# TOP_LEVEL.net
KiCad netlist of a schematic drawn in Altium Designer
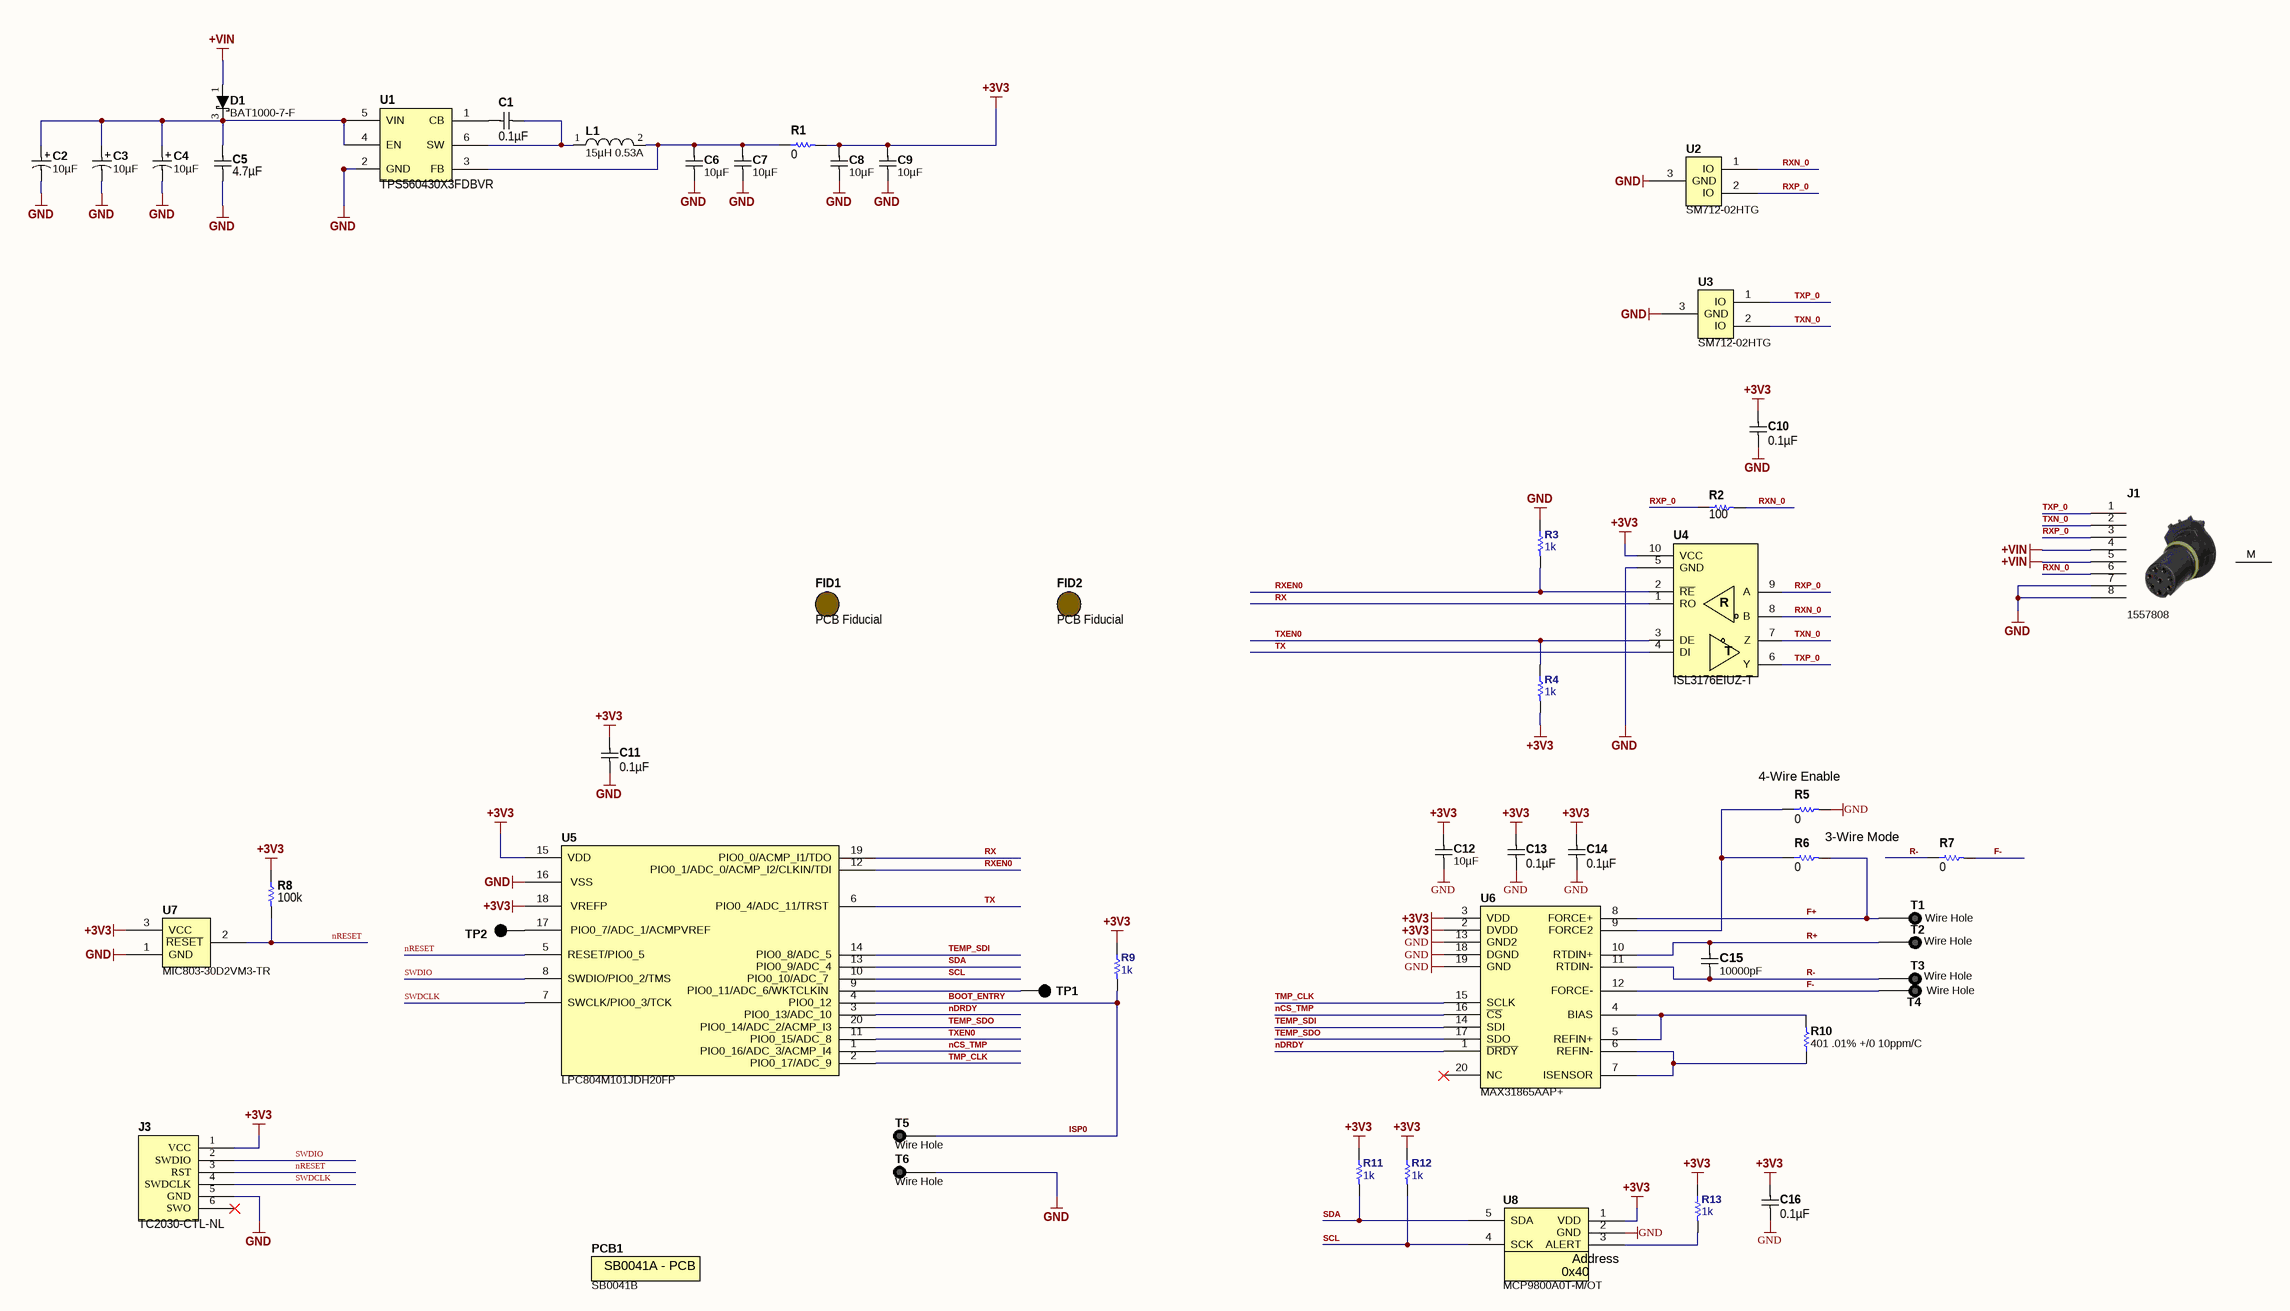
[diagram p0: TOP_LEVEL.SCHDOC]

(export (version "E")
  (design (tool "Eeschema 10.0.6"))
  (components
    (comp (ref "C1")
      (value "0.1µF")
      (footprint "C0603_0.90MM_MD")
      (description "CAP CER 0.1UF 50V X7R 0603")
      (fields
        (field (name "MANUFACTURER PART NUMBER") "CGA3E2X7R1H104K080AE")
        (field (name "MANUFACTURER") "TDK Corporation")
      )
      (libsource (lib "Capacitors - TDK- AEC-Q200") (part "C_2P_NP"))
    )
    (comp (ref "C2")
      (value "10µF")
      (footprint "C_ALU_B")
      (description "CAP ALUM 10UF 35V 20% SMD")
      (fields
        (field (name "MANUFACTURER PART NUMBER") "EEE-FK1V100UR")
        (field (name "MANUFACTURER") "Panasonic Electronic Components")
      )
      (libsource (lib "Capacitors - Panasonic - AluminumElectrolytic - AEC-Q200") (part "C_2P_P"))
    )
    (comp (ref "C3")
      (value "10µF")
      (footprint "C_ALU_B")
      (description "CAP ALUM 10UF 35V 20% SMD")
      (fields
        (field (name "MANUFACTURER PART NUMBER") "EEE-FK1V100UR")
        (field (name "MANUFACTURER") "Panasonic Electronic Components")
      )
      (libsource (lib "Capacitors - Panasonic - AluminumElectrolytic - AEC-Q200") (part "C_2P_P"))
    )
    (comp (ref "C4")
      (value "10µF")
      (footprint "C_ALU_B")
      (description "CAP ALUM 10UF 35V 20% SMD")
      (fields
        (field (name "MANUFACTURER PART NUMBER") "EEE-FK1V100UR")
        (field (name "MANUFACTURER") "Panasonic Electronic Components")
      )
      (libsource (lib "Capacitors - Panasonic - AluminumElectrolytic - AEC-Q200") (part "C_2P_P"))
    )
    (comp (ref "C5")
      (value "4.7µF")
      (footprint "C0805_1.50MM_MD")
      (description "CAP CER 4.7UF 35V X7R 0805")
      (fields
        (field (name "MANUFACTURER PART NUMBER") "CGA4J1X7R1V475K125AE")
        (field (name "MANUFACTURER") "TDK Corporation")
      )
      (libsource (lib "Capacitors - TDK- AEC-Q200") (part "C_2P_NP"))
    )
    (comp (ref "C6")
      (value "10µF")
      (footprint "C0805_1.25MM_MD")
      (description "CAP CER 10UF 6.3V X7R 0805")
      (fields
        (field (name "MANUFACTURER PART NUMBER") "CGA4J1X7R0J106K125AD")
        (field (name "MANUFACTURER") "TDK Corporation")
      )
      (libsource (lib "Capacitors - TDK- AEC-Q200") (part "C_2P_NP"))
    )
    (comp (ref "C7")
      (value "10µF")
      (footprint "C0805_1.25MM_MD")
      (description "CAP CER 10UF 6.3V X7R 0805")
      (fields
        (field (name "MANUFACTURER PART NUMBER") "CGA4J1X7R0J106K125AD")
        (field (name "MANUFACTURER") "TDK Corporation")
      )
      (libsource (lib "Capacitors - TDK- AEC-Q200") (part "C_2P_NP"))
    )
    (comp (ref "C8")
      (value "10µF")
      (footprint "C0805_1.25MM_MD")
      (description "CAP CER 10UF 6.3V X7R 0805")
      (fields
        (field (name "MANUFACTURER PART NUMBER") "CGA4J1X7R0J106K125AD")
        (field (name "MANUFACTURER") "TDK Corporation")
      )
      (libsource (lib "Capacitors - TDK- AEC-Q200") (part "C_2P_NP"))
    )
    (comp (ref "C9")
      (value "10µF")
      (footprint "C0805_1.25MM_MD")
      (description "CAP CER 10UF 6.3V X7R 0805")
      (fields
        (field (name "MANUFACTURER PART NUMBER") "CGA4J1X7R0J106K125AD")
        (field (name "MANUFACTURER") "TDK Corporation")
      )
      (libsource (lib "Capacitors - TDK- AEC-Q200") (part "C_2P_NP"))
    )
    (comp (ref "C10")
      (value "0.1µF")
      (footprint "C0603_0.90MM_MD")
      (description "CAP CER 0.1UF 50V X7R 0603")
      (fields
        (field (name "MANUFACTURER PART NUMBER") "CGA3E2X7R1H104K080AE")
        (field (name "MANUFACTURER") "TDK Corporation")
      )
      (libsource (lib "Capacitors - TDK- AEC-Q200") (part "C_2P_NP"))
    )
    (comp (ref "C11")
      (value "0.1µF")
      (footprint "C0603_0.90MM_MD")
      (description "CAP CER 0.1UF 50V X7R 0603")
      (fields
        (field (name "MANUFACTURER PART NUMBER") "CGA3E2X7R1H104K080AE")
        (field (name "MANUFACTURER") "TDK Corporation")
      )
      (libsource (lib "Capacitors - TDK- AEC-Q200") (part "C_2P_NP"))
    )
    (comp (ref "C12")
      (value "10µF")
      (footprint "C0805_1.25MM_MD")
      (description "CAP CER 10UF 6.3V X7R 0805")
      (fields
        (field (name "MANUFACTURER PART NUMBER") "CGA4J1X7R0J106K125AD")
        (field (name "MANUFACTURER") "TDK Corporation")
      )
      (libsource (lib "Capacitors - TDK- AEC-Q200") (part "C_2P_NP"))
    )
    (comp (ref "C13")
      (value "0.1µF")
      (footprint "C0603_0.90MM_MD")
      (description "CAP CER 0.1UF 50V X7R 0603")
      (fields
        (field (name "MANUFACTURER PART NUMBER") "CGA3E2X7R1H104K080AE")
        (field (name "MANUFACTURER") "TDK Corporation")
      )
      (libsource (lib "Capacitors - TDK- AEC-Q200") (part "C_2P_NP"))
    )
    (comp (ref "C14")
      (value "0.1µF")
      (footprint "C0603_0.90MM_MD")
      (description "CAP CER 0.1UF 50V X7R 0603")
      (fields
        (field (name "MANUFACTURER PART NUMBER") "CGA3E2X7R1H104K080AE")
        (field (name "MANUFACTURER") "TDK Corporation")
      )
      (libsource (lib "Capacitors - TDK- AEC-Q200") (part "C_2P_NP"))
    )
    (comp (ref "C15")
      (value "10000pF")
      (footprint "C0603_0.90MM_HD")
      (description "CAP CER 10000PF 50V X7R 0603")
      (fields
        (field (name "MANUFACTURER PART NUMBER") "AC0603KPX7R9BB103")
        (field (name "MANUFACTURER") "Yageo")
      )
      (libsource (lib "Capacitors - Yageo - AEC-Q200") (part "C_2P_NP"))
    )
    (comp (ref "C16")
      (value "0.1µF")
      (footprint "C0603_0.90MM_MD")
      (description "CAP CER 0.1UF 50V X7R 0603")
      (fields
        (field (name "MANUFACTURER PART NUMBER") "CGA3E2X7R1H104K080AE")
        (field (name "MANUFACTURER") "TDK Corporation")
      )
      (libsource (lib "Capacitors - TDK- AEC-Q200") (part "C_2P_NP"))
    )
    (comp (ref "D1")
      (value "BAT1000-7-F")
      (footprint "D_SOT-23-3_P")
      (description "DIODE SCHOTTKY 40V 1A SOT23")
      (fields (field (name "MANUFACTURER") "Diodes Inc"))
      (libsource (lib "Diodes") (part "DS_1A_3C"))
    )
    (comp (ref "FID1")
      (value "PCB Fiducial")
      (footprint "Fiducial 1mm - 2mm")
      (libsource (lib "eFiducial") (part "Fiducial"))
    )
    (comp (ref "FID2")
      (value "PCB Fiducial")
      (footprint "Fiducial 1mm - 2mm")
      (libsource (lib "eFiducial") (part "Fiducial"))
    )
    (comp (ref "J1")
      (value "1557808")
      (footprint "1557808")
      (description "Circular Metric Connectors SACC-CI-M12FS -8CON-L180-THR")
      (fields (field (name "MANUFACTURER") "Phoenix Contact"))
      (libsource (lib "eConnector_Phoenix_M12") (part "1557808"))
    )
    (comp (ref "J3")
      (value "TC2030‐CTL‐NL")
      (footprint "TC2030")
      (description "Tag Connect Pads - No latching Clips - ARM")
      (libsource (lib "eConnector") (part "TC2030‐CTL‐NL"))
    )
    (comp (ref "L1")
      (value "15µH 0.53A")
      (footprint "L_NRH3012")
      (description "Inductor 15µH 0.53A")
      (fields
        (field (name "MANUFACTURER PART NUMBER") "NRH3012T150MN")
        (field (name "MANUFACTURER") "Taiyo Yuden")
      )
      (libsource (lib "Inductors") (part "L_2P"))
    )
    (comp (ref "PCB1")
      (value "SB0041B")
      (description "SB0041 PCB Revision B")
      (fields (field (name "MANUFACTURER") "TZero"))
      (libsource (lib "ePCB") (part "SB0041B"))
    )
    (comp (ref "R1")
      (value "0")
      (footprint "R0603_0.55MM_MD")
      (description "RES 0.0 OHM 1/10W JUMP 0603 SMD")
      (fields
        (field (name "MANUFACTURER PART NUMBER") "ERJ-3GEY0R00V")
        (field (name "MANUFACTURER") "Panasonic Electronic Components")
      )
      (libsource (lib "Resistors - Panasonic - AEC-Q200") (part "R_2P"))
    )
    (comp (ref "R2")
      (value "100")
      (footprint "R0603_0.55MM_MD")
      (description "RES 100 OHM 1/10W 1% 0603 SMD")
      (fields
        (field (name "MANUFACTURER PART NUMBER") "ERJ-3EKF1000V")
        (field (name "MANUFACTURER") "Panasonic Electronic Components")
      )
      (libsource (lib "Resistors - Panasonic - AEC-Q200") (part "R_2P"))
    )
    (comp (ref "R3")
      (value "1k")
      (footprint "R0603_0.55MM_MD")
      (description "RES 1K OHM 1/10W 1% 0603 SMD")
      (fields
        (field (name "MANUFACTURER PART NUMBER") "ERJ-3EKF1001V")
        (field (name "MANUFACTURER") "Panasonic Electronic Components")
      )
      (libsource (lib "Resistors - Panasonic - AEC-Q200") (part "R_2P"))
    )
    (comp (ref "R4")
      (value "1k")
      (footprint "R0603_0.55MM_MD")
      (description "RES 1K OHM 1/10W 1% 0603 SMD")
      (fields
        (field (name "MANUFACTURER PART NUMBER") "ERJ-3EKF1001V")
        (field (name "MANUFACTURER") "Panasonic Electronic Components")
      )
      (libsource (lib "Resistors - Panasonic - AEC-Q200") (part "R_2P"))
    )
    (comp (ref "R5")
      (value "0")
      (footprint "R0603_0.55MM_MD")
      (description "RES 0.0 OHM 1/10W JUMP 0603 SMD")
      (fields
        (field (name "MANUFACTURER PART NUMBER") "ERJ-3GEY0R00V")
        (field (name "MANUFACTURER") "Panasonic Electronic Components")
      )
      (libsource (lib "Resistors - Panasonic - AEC-Q200") (part "R_2P"))
    )
    (comp (ref "R6")
      (value "0")
      (footprint "R0603_0.55MM_MD")
      (description "RES 0.0 OHM 1/10W JUMP 0603 SMD")
      (fields
        (field (name "MANUFACTURER PART NUMBER") "ERJ-3GEY0R00V")
        (field (name "MANUFACTURER") "Panasonic Electronic Components")
      )
      (libsource (lib "Resistors - Panasonic - AEC-Q200") (part "R_2P"))
    )
    (comp (ref "R7")
      (value "0")
      (footprint "R0603_0.55MM_MD")
      (description "RES 0.0 OHM 1/10W JUMP 0603 SMD")
      (fields
        (field (name "MANUFACTURER PART NUMBER") "ERJ-3GEY0R00V")
        (field (name "MANUFACTURER") "Panasonic Electronic Components")
      )
      (libsource (lib "Resistors - Panasonic - AEC-Q200") (part "R_2P"))
    )
    (comp (ref "R8")
      (value "100k")
      (footprint "R0603_0.55MM_MD")
      (description "RES 100K OHM 1/10W 1% 0603 SMD")
      (fields
        (field (name "MANUFACTURER PART NUMBER") "ERJ-3EKF1003V")
        (field (name "MANUFACTURER") "Panasonic Electronic Components")
      )
      (libsource (lib "Resistors - Panasonic - AEC-Q200") (part "R_2P"))
    )
    (comp (ref "R9")
      (value "1k")
      (footprint "R0603_0.55MM_MD")
      (description "RES 1K OHM 1/10W 1% 0603 SMD")
      (fields
        (field (name "MANUFACTURER PART NUMBER") "ERJ-3EKF1001V")
        (field (name "MANUFACTURER") "Panasonic Electronic Components")
      )
      (libsource (lib "Resistors - Panasonic - AEC-Q200") (part "R_2P"))
    )
    (comp (ref "R10")
      (value "401 .01% +/0 10ppm/C")
      (footprint "R0603_0.55MM_MD")
      (description "402 ±0.1% 0.15W Chip Resistor 0603 (1608 Metric) Anti-Sulfur, Automotive AEC-Q200 Thin Film")
      (fields
        (field (name "MANUFACTURER") "TE Connectivity")
        (field (name "MANUFACTURER PART NUMBER") "RQ73C1J402RBTD")
      )
      (libsource (lib "eResistors") (part "RQ73C1J402RBTD"))
    )
    (comp (ref "R11")
      (value "1k")
      (footprint "R0603_0.55MM_MD")
      (description "RES 1K OHM 1/10W 1% 0603 SMD")
      (fields
        (field (name "MANUFACTURER PART NUMBER") "ERJ-3EKF1001V")
        (field (name "MANUFACTURER") "Panasonic Electronic Components")
      )
      (libsource (lib "Resistors - Panasonic - AEC-Q200") (part "R_2P"))
    )
    (comp (ref "R12")
      (value "1k")
      (footprint "R0603_0.55MM_MD")
      (description "RES 1K OHM 1/10W 1% 0603 SMD")
      (fields
        (field (name "MANUFACTURER PART NUMBER") "ERJ-3EKF1001V")
        (field (name "MANUFACTURER") "Panasonic Electronic Components")
      )
      (libsource (lib "Resistors - Panasonic - AEC-Q200") (part "R_2P"))
    )
    (comp (ref "R13")
      (value "1k")
      (footprint "R0603_0.55MM_MD")
      (description "RES 1K OHM 1/10W 1% 0603 SMD")
      (fields
        (field (name "MANUFACTURER PART NUMBER") "ERJ-3EKF1001V")
        (field (name "MANUFACTURER") "Panasonic Electronic Components")
      )
      (libsource (lib "Resistors - Panasonic - AEC-Q200") (part "R_2P"))
    )
    (comp (ref "T1")
      (value "Wire Hole")
      (footprint "SOLDER_HOLE")
      (libsource (lib "eConnector") (part "SOLDER_HOLE"))
    )
    (comp (ref "T2")
      (value "Wire Hole")
      (footprint "SOLDER_HOLE")
      (libsource (lib "eConnector") (part "SOLDER_HOLE"))
    )
    (comp (ref "T3")
      (value "Wire Hole")
      (footprint "SOLDER_HOLE")
      (libsource (lib "eConnector") (part "SOLDER_HOLE"))
    )
    (comp (ref "T4")
      (value "Wire Hole")
      (footprint "SOLDER_HOLE")
      (libsource (lib "eConnector") (part "SOLDER_HOLE"))
    )
    (comp (ref "T5")
      (value "Wire Hole")
      (footprint "SOLDER_HOLE")
      (libsource (lib "eConnector") (part "SOLDER_HOLE"))
    )
    (comp (ref "T6")
      (value "Wire Hole")
      (footprint "SOLDER_HOLE")
      (libsource (lib "eConnector") (part "SOLDER_HOLE"))
    )
    (comp (ref "TP1")
      (value "SMT_TEST")
      (footprint "SMT_TP - 35")
      (libsource (lib "eTestPoint") (part "SMT_TEST"))
    )
    (comp (ref "TP2")
      (value "SMT_TEST")
      (footprint "SMT_TP - 35")
      (libsource (lib "eTestPoint") (part "SMT_TEST"))
    )
    (comp (ref "U1")
      (value "TPS560430X3FDBVR")
      (footprint "SOT95P245X145-6L")
      (description "Buck Switching Regulator IC Positive PWM 3.3V 1 Output 600mA SOT-23-6")
      (fields (field (name "MANUFACTURER") "Texas Instruments"))
      (libsource (lib "eIC_Regulator") (part "TPS560430X3FDBVR"))
    )
    (comp (ref "U2")
      (value "SM712-02HTG")
      (footprint "SOT-23")
      (fields (field (name "MANUFACTURER") "Littelfuse"))
      (libsource (lib "eDiode") (part "SM712-02HTG"))
    )
    (comp (ref "U3")
      (value "SM712-02HTG")
      (footprint "SOT-23")
      (fields (field (name "MANUFACTURER") "Littelfuse"))
      (libsource (lib "eDiode") (part "SM712-02HTG"))
    )
    (comp (ref "U4")
      (value "ISL3176EIUZ-T")
      (footprint "10 MSOP")
      (description "IC TXRX RS422/485 20MBPS 10MSOP")
      (fields (field (name "MANUFACTURER") "Intersil"))
      (libsource (lib "eIC") (part "ISL3176EIUZ-T"))
    )
    (comp (ref "U5")
      (value "LPC804M101JDH20FP")
      (footprint "TSOP65P640X105-20N")
      (description "MCU 32-bit ARM Cortex M0+ RISC 32KB Flash 3.3V 20-Pin TSSOP Tube")
      (fields (field (name "MANUFACTURER") "NXP Semiconductors"))
      (libsource (lib "eIC") (part "LPC804M101JDH20FP"))
    )
    (comp (ref "U6")
      (value "MAX31865AAP+")
      (footprint "SOP65P780X200-20N")
      (description "Temp Monitoring System (Sensor)  External Sensor SPI Output 20-SSOP")
      (fields (field (name "MANUFACTURER") "Maxim"))
      (libsource (lib "eIC") (part "MAX31865AAP+"))
    )
    (comp (ref "U7")
      (value "MIC803-30D2VM3-TR")
      (footprint "SOT-23")
      (description "3-Pin Microprocessor Supervisor Circuit w/ Open-Drain Reset Output, 3 SOT-23 - T/R")
      (fields (field (name "MANUFACTURER") "Microchip"))
      (libsource (lib "eIC") (part "MIC803-30D2VM3-TR"))
    )
    (comp (ref "U8")
      (value "MCP9800A0T-M/OT")
      (footprint "SOT23-5")
      (description "SENSOR TEMP I2C/SMBUS SOT23-5")
      (fields (field (name "MANUFACTURER") "Microchip Technology"))
      (libsource (lib "eIC") (part "MCP9800A0T-M/OT"))
    )
  )
  (nets
    (net (code "1") (name "+3V3") (class "Default")
      (node (ref "C10") (pin "2") (pinfunction "1_2") (pintype "passive"))
      (node (ref "C11") (pin "2") (pinfunction "1_2") (pintype "passive"))
      (node (ref "C12") (pin "2") (pinfunction "1_2") (pintype "passive"))
      (node (ref "C13") (pin "2") (pinfunction "1_2") (pintype "passive"))
      (node (ref "C14") (pin "2") (pinfunction "1_2") (pintype "passive"))
      (node (ref "C16") (pin "2") (pinfunction "1_2") (pintype "passive"))
      (node (ref "C8") (pin "2") (pinfunction "1_2") (pintype "passive"))
      (node (ref "C9") (pin "2") (pinfunction "1_2") (pintype "passive"))
      (node (ref "J3") (pin "1") (pinfunction "VCC_1") (pintype "passive"))
      (node (ref "R1") (pin "2") (pinfunction "2_2") (pintype "passive"))
      (node (ref "R11") (pin "1") (pinfunction "1_1") (pintype "passive"))
      (node (ref "R12") (pin "1") (pinfunction "1_1") (pintype "passive"))
      (node (ref "R13") (pin "1") (pinfunction "1_1") (pintype "passive"))
      (node (ref "R4") (pin "2") (pinfunction "2_2") (pintype "passive"))
      (node (ref "R8") (pin "1") (pinfunction "1_1") (pintype "passive"))
      (node (ref "R9") (pin "1") (pinfunction "1_1") (pintype "passive"))
      (node (ref "U4") (pin "10") (pinfunction "VCC_10") (pintype "passive"))
      (node (ref "U5") (pin "15") (pinfunction "VDD_15") (pintype "passive"))
      (node (ref "U5") (pin "18") (pinfunction "_VREFP_18") (pintype "passive"))
      (node (ref "U6") (pin "2") (pinfunction "DVDD_2") (pintype "passive"))
      (node (ref "U6") (pin "3") (pinfunction "VDD_3") (pintype "passive"))
      (node (ref "U7") (pin "3") (pinfunction "VCC_3") (pintype "passive"))
      (node (ref "U8") (pin "1") (pinfunction "VDD_1") (pintype "passive"))
    )
    (net (code "2") (name "+VIN") (class "Default")
      (node (ref "D1") (pin "1") (pinfunction "A_1") (pintype "passive"))
      (node (ref "J1") (pin "4") (pinfunction "4_4") (pintype "passive"))
      (node (ref "J1") (pin "5") (pinfunction "5_5") (pintype "passive"))
    )
    (net (code "3") (name "/BOOT_ENTRY") (class "Default")
      (node (ref "R9") (pin "2") (pinfunction "2_2") (pintype "passive"))
      (node (ref "T5") (pin "1") (pinfunction "1_1") (pintype "passive"))
      (node (ref "U5") (pin "4") (pinfunction "PIO0_12_4") (pintype "passive"))
    )
    (net (code "4") (name "/F+") (class "Default")
      (node (ref "R6") (pin "2") (pinfunction "2_2") (pintype "passive"))
      (node (ref "T1") (pin "1") (pinfunction "1_1") (pintype "passive"))
      (node (ref "U6") (pin "8") (pinfunction "FORCE+_8") (pintype "passive"))
    )
    (net (code "5") (name "/F-") (class "Default")
      (node (ref "R7") (pin "2") (pinfunction "2_2") (pintype "passive"))
      (node (ref "T4") (pin "1") (pinfunction "1_1") (pintype "passive"))
      (node (ref "U6") (pin "12") (pinfunction "FORCE-_12") (pintype "passive"))
    )
    (net (code "6") (name "/R+") (class "Default")
      (node (ref "C15") (pin "2") (pinfunction "1_2") (pintype "passive"))
      (node (ref "T2") (pin "1") (pinfunction "1_1") (pintype "passive"))
      (node (ref "U6") (pin "10") (pinfunction "RTDIN+_10") (pintype "passive"))
    )
    (net (code "7") (name "/R-") (class "Default")
      (node (ref "C15") (pin "1") (pinfunction "1_1") (pintype "passive"))
      (node (ref "R7") (pin "1") (pinfunction "1_1") (pintype "passive"))
      (node (ref "T3") (pin "1") (pinfunction "1_1") (pintype "passive"))
      (node (ref "U6") (pin "11") (pinfunction "RTDIN-_11") (pintype "passive"))
    )
    (net (code "8") (name "/RX") (class "Default")
      (node (ref "U4") (pin "1") (pinfunction "RO_1") (pintype "passive"))
      (node (ref "U5") (pin "19") (pinfunction "_PIO0_0/ACMP_I1/TDO_19") (pintype "passive"))
    )
    (net (code "9") (name "/RXEN0") (class "Default")
      (node (ref "R3") (pin "2") (pinfunction "2_2") (pintype "passive"))
      (node (ref "U4") (pin "2") (pinfunction "~{RE}_2") (pintype "passive"))
      (node (ref "U5") (pin "12") (pinfunction "PIO0_1/ADC_0/ACMP_I2/CLKIN/TDI_12") (pintype "passive"))
    )
    (net (code "10") (name "/RXN_0") (class "Default")
      (node (ref "J1") (pin "6") (pinfunction "6_6") (pintype "passive"))
      (node (ref "R2") (pin "2") (pinfunction "2_2") (pintype "passive"))
      (node (ref "U2") (pin "1") (pinfunction "IO_1") (pintype "passive"))
      (node (ref "U4") (pin "8") (pinfunction "B_8") (pintype "passive"))
    )
    (net (code "11") (name "/RXP_0") (class "Default")
      (node (ref "J1") (pin "3") (pinfunction "3_3") (pintype "passive"))
      (node (ref "R2") (pin "1") (pinfunction "1_1") (pintype "passive"))
      (node (ref "U2") (pin "2") (pinfunction "IO_2") (pintype "passive"))
      (node (ref "U4") (pin "9") (pinfunction "A_9") (pintype "passive"))
    )
    (net (code "12") (name "/SCL") (class "Default")
      (node (ref "R12") (pin "2") (pinfunction "2_2") (pintype "passive"))
      (node (ref "U5") (pin "10") (pinfunction "PIO0_10/ADC_7_10") (pintype "passive"))
      (node (ref "U8") (pin "4") (pinfunction "SCK_4") (pintype "passive"))
    )
    (net (code "13") (name "/SDA") (class "Default")
      (node (ref "R11") (pin "2") (pinfunction "2_2") (pintype "passive"))
      (node (ref "U5") (pin "13") (pinfunction "PIO0_9/ADC_4_13") (pintype "passive"))
      (node (ref "U8") (pin "5") (pinfunction "SDA_5") (pintype "passive"))
    )
    (net (code "14") (name "/SWDCLK") (class "Default")
      (node (ref "J3") (pin "4") (pinfunction "SWDCLK_4") (pintype "passive"))
      (node (ref "U5") (pin "7") (pinfunction "SWCLK/PIO0_3/TCK_7") (pintype "passive"))
    )
    (net (code "15") (name "/SWDIO") (class "Default")
      (node (ref "J3") (pin "2") (pinfunction "SWDIO_2") (pintype "passive"))
      (node (ref "U5") (pin "8") (pinfunction "SWDIO/PIO0_2/TMS_8") (pintype "passive"))
    )
    (net (code "16") (name "/TEMP_SDI") (class "Default")
      (node (ref "U5") (pin "14") (pinfunction "PIO0_8/ADC_5_14") (pintype "passive"))
      (node (ref "U6") (pin "14") (pinfunction "SDI_14") (pintype "passive"))
    )
    (net (code "17") (name "/TEMP_SDO") (class "Default")
      (node (ref "U5") (pin "20") (pinfunction "_PIO0_14/ADC_2/ACMP_I3_20") (pintype "passive"))
      (node (ref "U6") (pin "17") (pinfunction "SDO_17") (pintype "passive"))
    )
    (net (code "18") (name "/TMP_CLK") (class "Default")
      (node (ref "U5") (pin "2") (pinfunction "PIO0_17/ADC_9_2") (pintype "passive"))
      (node (ref "U6") (pin "15") (pinfunction "SCLK_15") (pintype "passive"))
    )
    (net (code "19") (name "/TX") (class "Default")
      (node (ref "U4") (pin "4") (pinfunction "DI_4") (pintype "passive"))
      (node (ref "U5") (pin "6") (pinfunction "PIO0_4/ADC_11/TRST_6") (pintype "passive"))
    )
    (net (code "20") (name "/TXEN0") (class "Default")
      (node (ref "R4") (pin "1") (pinfunction "1_1") (pintype "passive"))
      (node (ref "U4") (pin "3") (pinfunction "DE_3") (pintype "passive"))
      (node (ref "U5") (pin "11") (pinfunction "PIO0_15/ADC_8_11") (pintype "passive"))
    )
    (net (code "21") (name "/TXN_0") (class "Default")
      (node (ref "J1") (pin "2") (pinfunction "2_2") (pintype "passive"))
      (node (ref "U3") (pin "2") (pinfunction "IO_2") (pintype "passive"))
      (node (ref "U4") (pin "7") (pinfunction "Z_7") (pintype "passive"))
    )
    (net (code "22") (name "/TXP_0") (class "Default")
      (node (ref "J1") (pin "1") (pinfunction "1_1") (pintype "passive"))
      (node (ref "U3") (pin "1") (pinfunction "IO_1") (pintype "passive"))
      (node (ref "U4") (pin "6") (pinfunction "Y_6") (pintype "passive"))
    )
    (net (code "23") (name "/nCS_TMP") (class "Default")
      (node (ref "U5") (pin "1") (pinfunction "PIO0_16/ADC_3/ACMP_I4_1") (pintype "passive"))
      (node (ref "U6") (pin "16") (pinfunction "~{CS}_16") (pintype "passive"))
    )
    (net (code "24") (name "/nDRDY") (class "Default")
      (node (ref "U5") (pin "3") (pinfunction "PIO0_13/ADC_10_3") (pintype "passive"))
      (node (ref "U6") (pin "1") (pinfunction "~{DRDY}_1") (pintype "passive"))
    )
    (net (code "25") (name "/nRESET") (class "Default")
      (node (ref "J3") (pin "3") (pinfunction "RST_3") (pintype "passive"))
      (node (ref "R8") (pin "2") (pinfunction "2_2") (pintype "passive"))
      (node (ref "U5") (pin "5") (pinfunction "RESET/PIO0_5_5") (pintype "passive"))
      (node (ref "U7") (pin "2") (pinfunction "~{RESET}_2") (pintype "passive"))
    )
    (net (code "26") (name "GND") (class "Default")
      (node (ref "C10") (pin "1") (pinfunction "1_1") (pintype "passive"))
      (node (ref "C11") (pin "1") (pinfunction "1_1") (pintype "passive"))
      (node (ref "C12") (pin "1") (pinfunction "1_1") (pintype "passive"))
      (node (ref "C13") (pin "1") (pinfunction "1_1") (pintype "passive"))
      (node (ref "C14") (pin "1") (pinfunction "1_1") (pintype "passive"))
      (node (ref "C16") (pin "1") (pinfunction "1_1") (pintype "passive"))
      (node (ref "C2") (pin "2") (pinfunction "1_2") (pintype "passive"))
      (node (ref "C3") (pin "2") (pinfunction "1_2") (pintype "passive"))
      (node (ref "C4") (pin "2") (pinfunction "1_2") (pintype "passive"))
      (node (ref "C5") (pin "1") (pinfunction "1_1") (pintype "passive"))
      (node (ref "C6") (pin "1") (pinfunction "1_1") (pintype "passive"))
      (node (ref "C7") (pin "1") (pinfunction "1_1") (pintype "passive"))
      (node (ref "C8") (pin "1") (pinfunction "1_1") (pintype "passive"))
      (node (ref "C9") (pin "1") (pinfunction "1_1") (pintype "passive"))
      (node (ref "J1") (pin "7") (pinfunction "7_7") (pintype "passive"))
      (node (ref "J1") (pin "8") (pinfunction "8_8") (pintype "passive"))
      (node (ref "J3") (pin "5") (pinfunction "GND_5") (pintype "passive"))
      (node (ref "R3") (pin "1") (pinfunction "1_1") (pintype "passive"))
      (node (ref "R5") (pin "2") (pinfunction "2_2") (pintype "passive"))
      (node (ref "T6") (pin "1") (pinfunction "1_1") (pintype "passive"))
      (node (ref "U1") (pin "2") (pinfunction "GND_2") (pintype "passive"))
      (node (ref "U3") (pin "3") (pinfunction "GND_3") (pintype "passive"))
      (node (ref "U4") (pin "5") (pinfunction "GND_5") (pintype "passive"))
      (node (ref "U5") (pin "16") (pinfunction "_VSS_16") (pintype "passive"))
      (node (ref "U6") (pin "13") (pinfunction "GND2_13") (pintype "passive"))
      (node (ref "U6") (pin "18") (pinfunction "DGND_18") (pintype "passive"))
      (node (ref "U6") (pin "19") (pinfunction "GND_19") (pintype "passive"))
      (node (ref "U7") (pin "1") (pinfunction "GND_1") (pintype "passive"))
      (node (ref "U8") (pin "2") (pinfunction "GND_2") (pintype "passive"))
    )
    (net (code "27") (name "Net-(D1-K)") (class "Default")
      (node (ref "C2") (pin "1") (pinfunction "1_1") (pintype "passive"))
      (node (ref "C3") (pin "1") (pinfunction "1_1") (pintype "passive"))
      (node (ref "C4") (pin "1") (pinfunction "1_1") (pintype "passive"))
      (node (ref "C5") (pin "2") (pinfunction "1_2") (pintype "passive"))
      (node (ref "D1") (pin "3") (pinfunction "K_3") (pintype "passive"))
      (node (ref "U1") (pin "4") (pinfunction "EN_4") (pintype "passive"))
      (node (ref "U1") (pin "5") (pinfunction "VIN_5") (pintype "passive"))
    )
    (net (code "28") (name "Net-(U1-CB)") (class "Default")
      (node (ref "C1") (pin "2") (pinfunction "1_2") (pintype "passive"))
      (node (ref "U1") (pin "1") (pinfunction "CB_1") (pintype "passive"))
    )
    (net (code "29") (name "Net-(U1-FB)") (class "Default")
      (node (ref "C6") (pin "2") (pinfunction "1_2") (pintype "passive"))
      (node (ref "C7") (pin "2") (pinfunction "1_2") (pintype "passive"))
      (node (ref "L1") (pin "2") (pinfunction "2_2") (pintype "passive"))
      (node (ref "R1") (pin "1") (pinfunction "1_1") (pintype "passive"))
      (node (ref "U1") (pin "3") (pinfunction "FB_3") (pintype "passive"))
    )
    (net (code "30") (name "Net-(U1-SW)") (class "Default")
      (node (ref "C1") (pin "1") (pinfunction "1_1") (pintype "passive"))
      (node (ref "L1") (pin "1") (pinfunction "1_1") (pintype "passive"))
      (node (ref "U1") (pin "6") (pinfunction "SW_6") (pintype "passive"))
    )
    (net (code "31") (name "Net-(U5-PIO0_11{slash}ADC_6{slash}WKTCLKIN)") (class "Default")
      (node (ref "TP1") (pin "1") (pinfunction "1_1") (pintype "passive"))
      (node (ref "U5") (pin "9") (pinfunction "PIO0_11/ADC_6/WKTCLKIN_9") (pintype "passive"))
    )
    (net (code "32") (name "Net-(U5-_PIO0_7{slash}ADC_1{slash}ACMPVREF)") (class "Default")
      (node (ref "TP2") (pin "1") (pinfunction "1_1") (pintype "passive"))
      (node (ref "U5") (pin "17") (pinfunction "_PIO0_7/ADC_1/ACMPVREF_17") (pintype "passive"))
    )
    (net (code "33") (name "Net-(U6-BIAS)") (class "Default")
      (node (ref "R10") (pin "2") (pinfunction "2_2") (pintype "passive"))
      (node (ref "U6") (pin "4") (pinfunction "BIAS_4") (pintype "passive"))
      (node (ref "U6") (pin "5") (pinfunction "REFIN+_5") (pintype "passive"))
    )
    (net (code "34") (name "Net-(U6-FORCE2)") (class "Default")
      (node (ref "R5") (pin "1") (pinfunction "1_1") (pintype "passive"))
      (node (ref "R6") (pin "1") (pinfunction "1_1") (pintype "passive"))
      (node (ref "U6") (pin "9") (pinfunction "FORCE2_9") (pintype "passive"))
    )
    (net (code "35") (name "Net-(U6-ISENSOR)") (class "Default")
      (node (ref "R10") (pin "1") (pinfunction "1_1") (pintype "passive"))
      (node (ref "U6") (pin "6") (pinfunction "REFIN-_6") (pintype "passive"))
      (node (ref "U6") (pin "7") (pinfunction "ISENSOR_7") (pintype "passive"))
    )
    (net (code "36") (name "Net-(U8-ALERT)") (class "Default")
      (node (ref "R13") (pin "2") (pinfunction "2_2") (pintype "passive"))
      (node (ref "U8") (pin "3") (pinfunction "ALERT_3") (pintype "passive"))
    )
    (net (code "37") (name "unconnected-(J1-PadM)") (class "Default")
      (node (ref "J1") (pin "M") (pinfunction "M_M") (pintype "passive"))
    )
    (net (code "38") (name "unconnected-(J3-SWO-Pad6)") (class "Default")
      (node (ref "J3") (pin "6") (pinfunction "SWO_6") (pintype "passive+no_connect"))
    )
    (net (code "39") (name "unconnected-(U2-GND-Pad3)") (class "Default")
      (node (ref "U2") (pin "3") (pinfunction "GND_3") (pintype "passive"))
    )
    (net (code "40") (name "unconnected-(U6-NC-Pad20)") (class "Default")
      (node (ref "U6") (pin "20") (pinfunction "NC_20") (pintype "passive+no_connect"))
    )
  )
)
